# VDC.net
KiCad netlist of a schematic drawn in EAGLE
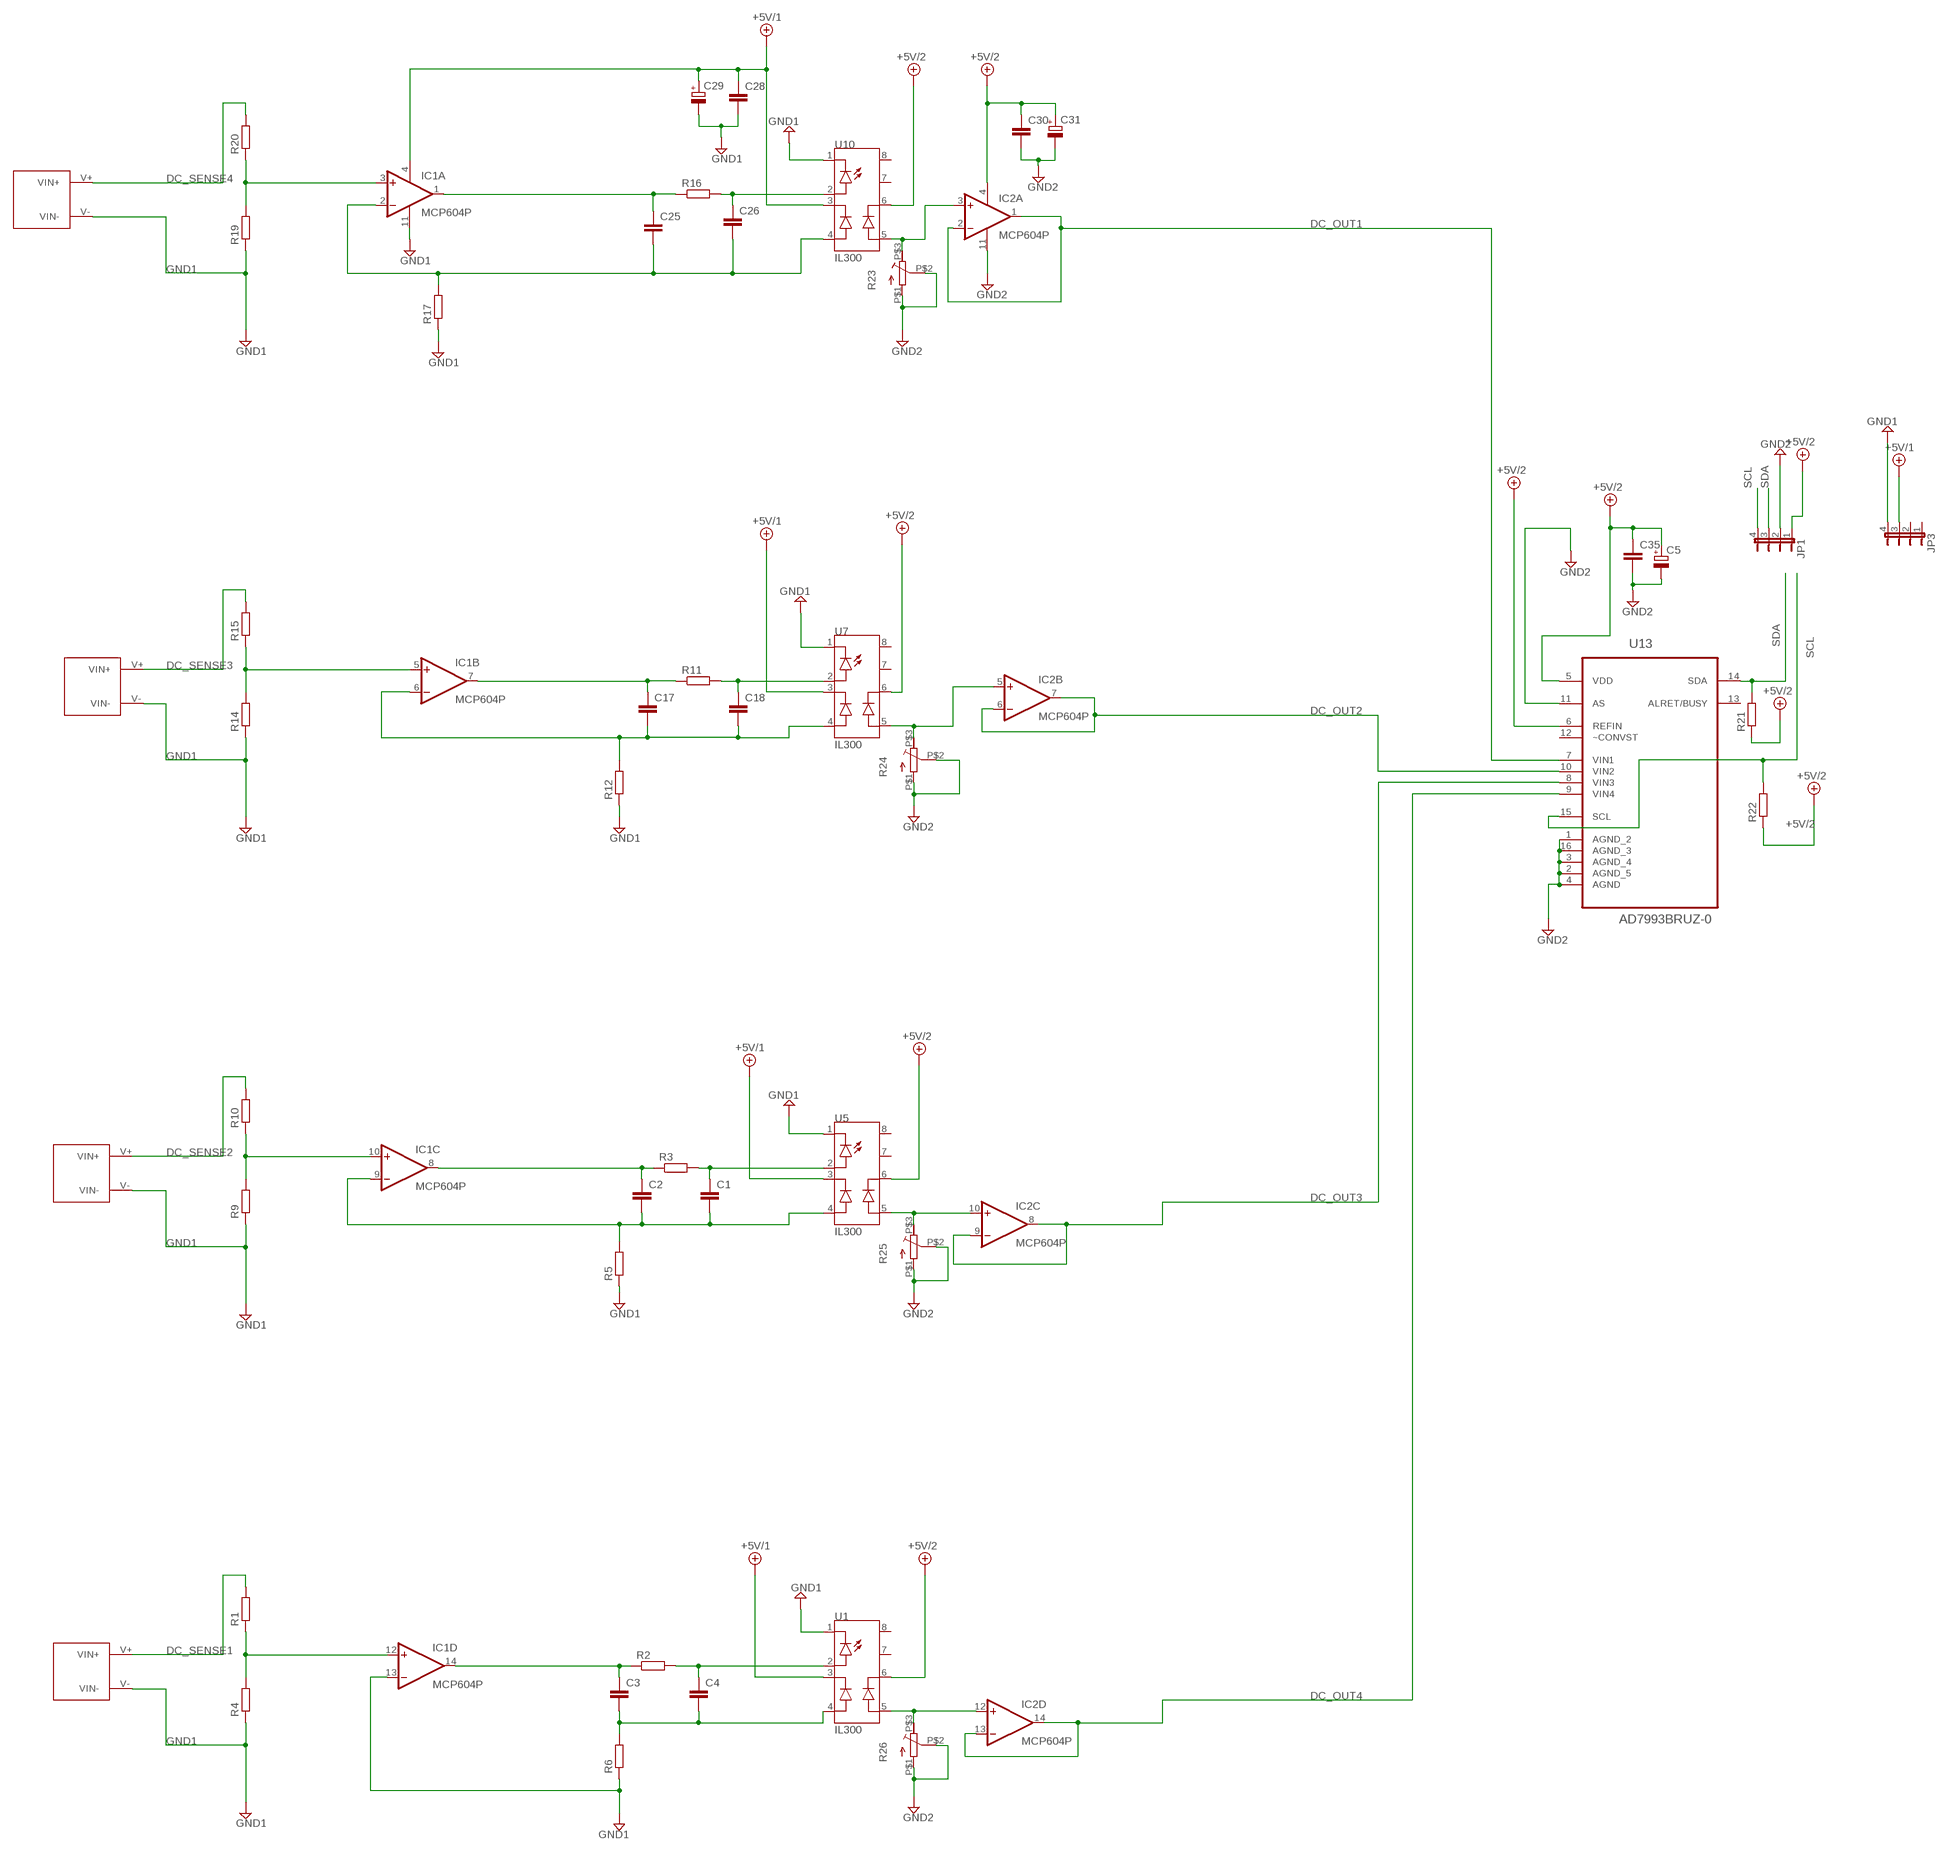
[diagram p0: schematic, sheet 1]

(export (version "E")
  (design (tool "Eeschema 10.0.6"))
  (components
    (comp (ref "C1")
      (value "C-EU025-040X050")
      (footprint "eagle-import:C025-040X050")
      (libsource (lib "eagle-import") (part "C-EU025-040X050"))
    )
    (comp (ref "C2")
      (value "C-EU025-040X050")
      (footprint "eagle-import:C025-040X050")
      (libsource (lib "eagle-import") (part "C-EU025-040X050"))
    )
    (comp (ref "C3")
      (value "C-EU025-040X050")
      (footprint "eagle-import:C025-040X050")
      (libsource (lib "eagle-import") (part "C-EU025-040X050"))
    )
    (comp (ref "C4")
      (value "C-EU025-040X050")
      (footprint "eagle-import:C025-040X050")
      (libsource (lib "eagle-import") (part "C-EU025-040X050"))
    )
    (comp (ref "C5")
      (value "CPOL-EUE2-4")
      (footprint "eagle-import:E2-4")
      (libsource (lib "eagle-import") (part "CPOL-EUE2-4"))
    )
    (comp (ref "C17")
      (value "C-EU025-040X050")
      (footprint "eagle-import:C025-040X050")
      (libsource (lib "eagle-import") (part "C-EU025-040X050"))
    )
    (comp (ref "C18")
      (value "C-EU025-040X050")
      (footprint "eagle-import:C025-040X050")
      (libsource (lib "eagle-import") (part "C-EU025-040X050"))
    )
    (comp (ref "C25")
      (value "C-EU025-040X050")
      (footprint "eagle-import:C025-040X050")
      (libsource (lib "eagle-import") (part "C-EU025-040X050"))
    )
    (comp (ref "C26")
      (value "C-EU025-040X050")
      (footprint "eagle-import:C025-040X050")
      (libsource (lib "eagle-import") (part "C-EU025-040X050"))
    )
    (comp (ref "C28")
      (value "C-EU025-040X050")
      (footprint "eagle-import:C025-040X050")
      (libsource (lib "eagle-import") (part "C-EU025-040X050"))
    )
    (comp (ref "C29")
      (value "CPOL-EUE2-5")
      (footprint "eagle-import:E2-5")
      (libsource (lib "eagle-import") (part "CPOL-EUE2-5"))
    )
    (comp (ref "C30")
      (value "C-EU025-040X050")
      (footprint "eagle-import:C025-040X050")
      (libsource (lib "eagle-import") (part "C-EU025-040X050"))
    )
    (comp (ref "C31")
      (value "CPOL-EUE2-5")
      (footprint "eagle-import:E2-5")
      (libsource (lib "eagle-import") (part "CPOL-EUE2-5"))
    )
    (comp (ref "C35")
      (value "C-EU025-025X050")
      (footprint "eagle-import:C025-025X050")
      (libsource (lib "eagle-import") (part "C-EU025-025X050"))
    )
    (comp (ref "IC1")
      (value "MCP604P")
      (footprint "eagle-import:DIL14")
      (libsource (lib "eagle-import") (part "MCP604P"))
    )
    (comp (ref "IC2")
      (value "MCP604P")
      (footprint "eagle-import:DIL14")
      (libsource (lib "eagle-import") (part "MCP604P"))
    )
    (comp (ref "JP1")
      (value "JP4E")
      (footprint "eagle-import:JP4")
      (libsource (lib "eagle-import") (part "JP4E"))
    )
    (comp (ref "JP3")
      (value "JP4E")
      (footprint "eagle-import:JP4")
      (libsource (lib "eagle-import") (part "JP4E"))
    )
    (comp (ref "R1")
      (value "R-EU_0207/10")
      (footprint "eagle-import:0207_10")
      (libsource (lib "eagle-import") (part "R-EU_0207/10"))
    )
    (comp (ref "R2")
      (value "R-EU_0207/10")
      (footprint "eagle-import:0207_10")
      (libsource (lib "eagle-import") (part "R-EU_0207/10"))
    )
    (comp (ref "R3")
      (value "R-EU_0207/10")
      (footprint "eagle-import:0207_10")
      (libsource (lib "eagle-import") (part "R-EU_0207/10"))
    )
    (comp (ref "R4")
      (value "R-EU_0207/10")
      (footprint "eagle-import:0207_10")
      (libsource (lib "eagle-import") (part "R-EU_0207/10"))
    )
    (comp (ref "R5")
      (value "R-EU_0207/10")
      (footprint "eagle-import:0207_10")
      (libsource (lib "eagle-import") (part "R-EU_0207/10"))
    )
    (comp (ref "R6")
      (value "R-EU_0207/10")
      (footprint "eagle-import:0207_10")
      (libsource (lib "eagle-import") (part "R-EU_0207/10"))
    )
    (comp (ref "R9")
      (value "R-EU_0207/10")
      (footprint "eagle-import:0207_10")
      (libsource (lib "eagle-import") (part "R-EU_0207/10"))
    )
    (comp (ref "R10")
      (value "R-EU_0207/10")
      (footprint "eagle-import:0207_10")
      (libsource (lib "eagle-import") (part "R-EU_0207/10"))
    )
    (comp (ref "R11")
      (value "R-EU_0207/10")
      (footprint "eagle-import:0207_10")
      (libsource (lib "eagle-import") (part "R-EU_0207/10"))
    )
    (comp (ref "R12")
      (value "R-EU_0207/10")
      (footprint "eagle-import:0207_10")
      (libsource (lib "eagle-import") (part "R-EU_0207/10"))
    )
    (comp (ref "R14")
      (value "R-EU_0207/10")
      (footprint "eagle-import:0207_10")
      (libsource (lib "eagle-import") (part "R-EU_0207/10"))
    )
    (comp (ref "R15")
      (value "R-EU_0207/10")
      (footprint "eagle-import:0207_10")
      (libsource (lib "eagle-import") (part "R-EU_0207/10"))
    )
    (comp (ref "R16")
      (value "R-EU_0207/10")
      (footprint "eagle-import:0207_10")
      (libsource (lib "eagle-import") (part "R-EU_0207/10"))
    )
    (comp (ref "R17")
      (value "R-EU_0207/10")
      (footprint "eagle-import:0207_10")
      (libsource (lib "eagle-import") (part "R-EU_0207/10"))
    )
    (comp (ref "R19")
      (value "R-EU_0207/10")
      (footprint "eagle-import:0207_10")
      (libsource (lib "eagle-import") (part "R-EU_0207/10"))
    )
    (comp (ref "R20")
      (value "R-EU_0207/10")
      (footprint "eagle-import:0207_10")
      (libsource (lib "eagle-import") (part "R-EU_0207/10"))
    )
    (comp (ref "R21")
      (value "R-EU_0207/10")
      (footprint "eagle-import:0207_10")
      (libsource (lib "eagle-import") (part "R-EU_0207/10"))
    )
    (comp (ref "R22")
      (value "R-EU_0207/10")
      (footprint "eagle-import:0207_10")
      (libsource (lib "eagle-import") (part "R-EU_0207/10"))
    )
    (comp (ref "R23")
      (value "R-TRIMM")
      (footprint "eagle-import:IRG2014TRIM")
      (libsource (lib "eagle-import") (part "R-TRIMM"))
    )
    (comp (ref "R24")
      (value "R-TRIMM")
      (footprint "eagle-import:IRG2014TRIM")
      (libsource (lib "eagle-import") (part "R-TRIMM"))
    )
    (comp (ref "R25")
      (value "R-TRIMM")
      (footprint "eagle-import:IRG2014TRIM")
      (libsource (lib "eagle-import") (part "R-TRIMM"))
    )
    (comp (ref "R26")
      (value "R-TRIMM")
      (footprint "eagle-import:IRG2014TRIM")
      (libsource (lib "eagle-import") (part "R-TRIMM"))
    )
    (comp (ref "U$5")
      (value "INPUT_VOLTAGE_CONNECTOR")
      (footprint "eagle-import:INPUT_VOLTAGE_CONNECTOR")
      (libsource (lib "eagle-import") (part "INPUT_VOLTAGE_CONNECTOR"))
    )
    (comp (ref "U$6")
      (value "INPUT_VOLTAGE_CONNECTOR")
      (footprint "eagle-import:INPUT_VOLTAGE_CONNECTOR")
      (libsource (lib "eagle-import") (part "INPUT_VOLTAGE_CONNECTOR"))
    )
    (comp (ref "U$7")
      (value "INPUT_VOLTAGE_CONNECTOR")
      (footprint "eagle-import:INPUT_VOLTAGE_CONNECTOR")
      (libsource (lib "eagle-import") (part "INPUT_VOLTAGE_CONNECTOR"))
    )
    (comp (ref "U$8")
      (value "INPUT_VOLTAGE_CONNECTOR")
      (footprint "eagle-import:INPUT_VOLTAGE_CONNECTOR")
      (libsource (lib "eagle-import") (part "INPUT_VOLTAGE_CONNECTOR"))
    )
    (comp (ref "U1")
      (value "IL300")
      (footprint "eagle-import:DIL08")
      (libsource (lib "eagle-import") (part "IL300"))
    )
    (comp (ref "U5")
      (value "IL300")
      (footprint "eagle-import:DIL08")
      (libsource (lib "eagle-import") (part "IL300"))
    )
    (comp (ref "U7")
      (value "IL300")
      (footprint "eagle-import:DIL08")
      (libsource (lib "eagle-import") (part "IL300"))
    )
    (comp (ref "U10")
      (value "IL300")
      (footprint "eagle-import:DIL08")
      (libsource (lib "eagle-import") (part "IL300"))
    )
    (comp (ref "U13")
      (value "AD7993BRUZ-0")
      (footprint "eagle-import:SOP65P640X120-16N")
      (libsource (lib "eagle-import") (part "AD7993BRUZ-0"))
    )
  )
  (nets
    (net (code "1") (name "+5V{slash}1") (class "Default")
      (node (ref "C28") (pin "1") (pinfunction "1_1") (pintype "passive"))
      (node (ref "C29") (pin "+") (pinfunction "+_+") (pintype "passive"))
      (node (ref "IC1") (pin "4") (pinfunction "V+_4") (pintype "power_in"))
      (node (ref "JP3") (pin "3") (pinfunction "3_3") (pintype "passive"))
      (node (ref "U1") (pin "3") (pinfunction "C_FB_3") (pintype "passive"))
      (node (ref "U10") (pin "3") (pinfunction "C_FB_3") (pintype "passive"))
      (node (ref "U5") (pin "3") (pinfunction "C_FB_3") (pintype "passive"))
      (node (ref "U7") (pin "3") (pinfunction "C_FB_3") (pintype "passive"))
    )
    (net (code "2") (name "+5V{slash}2") (class "Default")
      (node (ref "C30") (pin "1") (pinfunction "1_1") (pintype "passive"))
      (node (ref "C31") (pin "+") (pinfunction "+_+") (pintype "passive"))
      (node (ref "C35") (pin "1") (pinfunction "1_1") (pintype "passive"))
      (node (ref "C5") (pin "+") (pinfunction "+_+") (pintype "passive"))
      (node (ref "IC2") (pin "4") (pinfunction "V+_4") (pintype "power_in"))
      (node (ref "JP1") (pin "1") (pinfunction "1_1") (pintype "passive"))
      (node (ref "R21") (pin "1") (pinfunction "1_1") (pintype "passive"))
      (node (ref "R22") (pin "1") (pinfunction "1_1") (pintype "passive"))
      (node (ref "U1") (pin "6") (pinfunction "C_OUT_6") (pintype "passive"))
      (node (ref "U10") (pin "6") (pinfunction "C_OUT_6") (pintype "passive"))
      (node (ref "U13") (pin "5") (pinfunction "VDD_5") (pintype "power_in"))
      (node (ref "U13") (pin "6") (pinfunction "REFIN_6") (pintype "input"))
      (node (ref "U5") (pin "6") (pinfunction "C_OUT_6") (pintype "passive"))
      (node (ref "U7") (pin "6") (pinfunction "C_OUT_6") (pintype "passive"))
    )
    (net (code "3") (name "/DC_OUT1") (class "Default")
      (node (ref "IC2") (pin "1") (pinfunction "OUT_1") (pintype "output"))
      (node (ref "IC2") (pin "2") (pinfunction "-IN_2") (pintype "input"))
      (node (ref "U13") (pin "7") (pinfunction "VIN1_7") (pintype "input"))
    )
    (net (code "4") (name "/DC_OUT2") (class "Default")
      (node (ref "IC2") (pin "6") (pinfunction "-IN_6") (pintype "input"))
      (node (ref "IC2") (pin "7") (pinfunction "OUT_7") (pintype "output"))
      (node (ref "U13") (pin "10") (pinfunction "VIN2_10") (pintype "input"))
    )
    (net (code "5") (name "/DC_OUT3") (class "Default")
      (node (ref "IC2") (pin "8") (pinfunction "OUT_8") (pintype "output"))
      (node (ref "IC2") (pin "9") (pinfunction "-IN_9") (pintype "input"))
      (node (ref "U13") (pin "8") (pinfunction "VIN3_8") (pintype "input"))
    )
    (net (code "6") (name "/DC_OUT4") (class "Default")
      (node (ref "IC2") (pin "13") (pinfunction "-IN_13") (pintype "input"))
      (node (ref "IC2") (pin "14") (pinfunction "OUT_14") (pintype "output"))
      (node (ref "U13") (pin "9") (pinfunction "VIN4_9") (pintype "input"))
    )
    (net (code "7") (name "/DC_SENSE1") (class "Default")
      (node (ref "R1") (pin "2") (pinfunction "2_2") (pintype "passive"))
      (node (ref "U$8") (pin "V+") (pinfunction "VIN+_V+") (pintype "bidirectional"))
    )
    (net (code "8") (name "/DC_SENSE2") (class "Default")
      (node (ref "R10") (pin "2") (pinfunction "2_2") (pintype "passive"))
      (node (ref "U$7") (pin "V+") (pinfunction "VIN+_V+") (pintype "bidirectional"))
    )
    (net (code "9") (name "/DC_SENSE3") (class "Default")
      (node (ref "R15") (pin "2") (pinfunction "2_2") (pintype "passive"))
      (node (ref "U$6") (pin "V+") (pinfunction "VIN+_V+") (pintype "bidirectional"))
    )
    (net (code "10") (name "/DC_SENSE4") (class "Default")
      (node (ref "R20") (pin "2") (pinfunction "2_2") (pintype "passive"))
      (node (ref "U$5") (pin "V+") (pinfunction "VIN+_V+") (pintype "bidirectional"))
    )
    (net (code "11") (name "/SCL") (class "Default")
      (node (ref "JP1") (pin "4") (pinfunction "4_4") (pintype "passive"))
      (node (ref "R22") (pin "2") (pinfunction "2_2") (pintype "passive"))
      (node (ref "U13") (pin "15") (pinfunction "SCL_15") (pintype "input"))
    )
    (net (code "12") (name "/SDA") (class "Default")
      (node (ref "JP1") (pin "3") (pinfunction "3_3") (pintype "passive"))
      (node (ref "R21") (pin "2") (pinfunction "2_2") (pintype "passive"))
      (node (ref "U13") (pin "14") (pinfunction "SDA_14") (pintype "bidirectional"))
    )
    (net (code "13") (name "GND1") (class "Default")
      (node (ref "C28") (pin "2") (pinfunction "2_2") (pintype "passive"))
      (node (ref "C29") (pin "-") (pinfunction "-_-") (pintype "passive"))
      (node (ref "IC1") (pin "11") (pinfunction "V-_11") (pintype "power_in"))
      (node (ref "IC1") (pin "13") (pinfunction "-IN_13") (pintype "input"))
      (node (ref "JP3") (pin "4") (pinfunction "4_4") (pintype "passive"))
      (node (ref "R12") (pin "1") (pinfunction "1_1") (pintype "passive"))
      (node (ref "R14") (pin "1") (pinfunction "1_1") (pintype "passive"))
      (node (ref "R17") (pin "1") (pinfunction "1_1") (pintype "passive"))
      (node (ref "R19") (pin "1") (pinfunction "1_1") (pintype "passive"))
      (node (ref "R4") (pin "1") (pinfunction "1_1") (pintype "passive"))
      (node (ref "R5") (pin "1") (pinfunction "1_1") (pintype "passive"))
      (node (ref "R6") (pin "1") (pinfunction "1_1") (pintype "passive"))
      (node (ref "R9") (pin "1") (pinfunction "1_1") (pintype "passive"))
      (node (ref "U$5") (pin "V-") (pinfunction "VIN-_V-") (pintype "bidirectional"))
      (node (ref "U$6") (pin "V-") (pinfunction "VIN-_V-") (pintype "bidirectional"))
      (node (ref "U$7") (pin "V-") (pinfunction "VIN-_V-") (pintype "bidirectional"))
      (node (ref "U$8") (pin "V-") (pinfunction "VIN-_V-") (pintype "bidirectional"))
      (node (ref "U1") (pin "1") (pinfunction "C_LED_1") (pintype "passive"))
      (node (ref "U10") (pin "1") (pinfunction "C_LED_1") (pintype "passive"))
      (node (ref "U5") (pin "1") (pinfunction "C_LED_1") (pintype "passive"))
      (node (ref "U7") (pin "1") (pinfunction "C_LED_1") (pintype "passive"))
    )
    (net (code "14") (name "GND2") (class "Default")
      (node (ref "C30") (pin "2") (pinfunction "2_2") (pintype "passive"))
      (node (ref "C31") (pin "-") (pinfunction "-_-") (pintype "passive"))
      (node (ref "C35") (pin "2") (pinfunction "2_2") (pintype "passive"))
      (node (ref "C5") (pin "-") (pinfunction "-_-") (pintype "passive"))
      (node (ref "IC2") (pin "11") (pinfunction "V-_11") (pintype "power_in"))
      (node (ref "JP1") (pin "2") (pinfunction "2_2") (pintype "passive"))
      (node (ref "R23") (pin "P$1") (pinfunction "A_P$1") (pintype "passive"))
      (node (ref "R23") (pin "P$2") (pinfunction "S_P$2") (pintype "passive"))
      (node (ref "R24") (pin "P$1") (pinfunction "A_P$1") (pintype "passive"))
      (node (ref "R24") (pin "P$2") (pinfunction "S_P$2") (pintype "passive"))
      (node (ref "R25") (pin "P$1") (pinfunction "A_P$1") (pintype "passive"))
      (node (ref "R25") (pin "P$2") (pinfunction "S_P$2") (pintype "passive"))
      (node (ref "R26") (pin "P$1") (pinfunction "A_P$1") (pintype "passive"))
      (node (ref "R26") (pin "P$2") (pinfunction "S_P$2") (pintype "passive"))
      (node (ref "U13") (pin "1") (pinfunction "AGND_2_1") (pintype "passive"))
      (node (ref "U13") (pin "11") (pinfunction "AS_11") (pintype "input"))
      (node (ref "U13") (pin "16") (pinfunction "AGND_3_16") (pintype "passive"))
      (node (ref "U13") (pin "2") (pinfunction "AGND_5_2") (pintype "passive"))
      (node (ref "U13") (pin "3") (pinfunction "AGND_4_3") (pintype "passive"))
      (node (ref "U13") (pin "4") (pinfunction "AGND_4") (pintype "passive"))
    )
    (net (code "15") (name "Net-(IC1A-+IN)") (class "Default")
      (node (ref "IC1") (pin "3") (pinfunction "+IN_3") (pintype "input"))
      (node (ref "R19") (pin "2") (pinfunction "2_2") (pintype "passive"))
      (node (ref "R20") (pin "1") (pinfunction "1_1") (pintype "passive"))
    )
    (net (code "16") (name "Net-(IC1A--IN)") (class "Default")
      (node (ref "C25") (pin "2") (pinfunction "2_2") (pintype "passive"))
      (node (ref "C26") (pin "2") (pinfunction "2_2") (pintype "passive"))
      (node (ref "IC1") (pin "2") (pinfunction "-IN_2") (pintype "input"))
      (node (ref "R17") (pin "2") (pinfunction "2_2") (pintype "passive"))
      (node (ref "U10") (pin "4") (pinfunction "A_FB_4") (pintype "passive"))
    )
    (net (code "17") (name "Net-(IC1A-OUT)") (class "Default")
      (node (ref "C25") (pin "1") (pinfunction "1_1") (pintype "passive"))
      (node (ref "IC1") (pin "1") (pinfunction "OUT_1") (pintype "output"))
      (node (ref "R16") (pin "1") (pinfunction "1_1") (pintype "passive"))
    )
    (net (code "18") (name "Net-(IC1B-+IN)") (class "Default")
      (node (ref "IC1") (pin "5") (pinfunction "+IN_5") (pintype "input"))
      (node (ref "R14") (pin "2") (pinfunction "2_2") (pintype "passive"))
      (node (ref "R15") (pin "1") (pinfunction "1_1") (pintype "passive"))
    )
    (net (code "19") (name "Net-(IC1B--IN)") (class "Default")
      (node (ref "C17") (pin "2") (pinfunction "2_2") (pintype "passive"))
      (node (ref "C18") (pin "2") (pinfunction "2_2") (pintype "passive"))
      (node (ref "IC1") (pin "6") (pinfunction "-IN_6") (pintype "input"))
      (node (ref "R12") (pin "2") (pinfunction "2_2") (pintype "passive"))
      (node (ref "U7") (pin "4") (pinfunction "A_FB_4") (pintype "passive"))
    )
    (net (code "20") (name "Net-(IC1B-OUT)") (class "Default")
      (node (ref "C17") (pin "1") (pinfunction "1_1") (pintype "passive"))
      (node (ref "IC1") (pin "7") (pinfunction "OUT_7") (pintype "output"))
      (node (ref "R11") (pin "1") (pinfunction "1_1") (pintype "passive"))
    )
    (net (code "21") (name "Net-(IC1C-+IN)") (class "Default")
      (node (ref "IC1") (pin "10") (pinfunction "+IN_10") (pintype "input"))
      (node (ref "R10") (pin "1") (pinfunction "1_1") (pintype "passive"))
      (node (ref "R9") (pin "2") (pinfunction "2_2") (pintype "passive"))
    )
    (net (code "22") (name "Net-(IC1C--IN)") (class "Default")
      (node (ref "C1") (pin "2") (pinfunction "2_2") (pintype "passive"))
      (node (ref "C2") (pin "2") (pinfunction "2_2") (pintype "passive"))
      (node (ref "IC1") (pin "9") (pinfunction "-IN_9") (pintype "input"))
      (node (ref "R5") (pin "2") (pinfunction "2_2") (pintype "passive"))
      (node (ref "U5") (pin "4") (pinfunction "A_FB_4") (pintype "passive"))
    )
    (net (code "23") (name "Net-(IC1C-OUT)") (class "Default")
      (node (ref "C2") (pin "1") (pinfunction "1_1") (pintype "passive"))
      (node (ref "IC1") (pin "8") (pinfunction "OUT_8") (pintype "output"))
      (node (ref "R3") (pin "1") (pinfunction "1_1") (pintype "passive"))
    )
    (net (code "24") (name "Net-(IC1D-+IN)") (class "Default")
      (node (ref "IC1") (pin "12") (pinfunction "+IN_12") (pintype "input"))
      (node (ref "R1") (pin "1") (pinfunction "1_1") (pintype "passive"))
      (node (ref "R4") (pin "2") (pinfunction "2_2") (pintype "passive"))
    )
    (net (code "25") (name "Net-(IC1D-OUT)") (class "Default")
      (node (ref "C3") (pin "1") (pinfunction "1_1") (pintype "passive"))
      (node (ref "IC1") (pin "14") (pinfunction "OUT_14") (pintype "output"))
      (node (ref "R2") (pin "1") (pinfunction "1_1") (pintype "passive"))
    )
    (net (code "26") (name "Net-(IC2A-+IN)") (class "Default")
      (node (ref "IC2") (pin "3") (pinfunction "+IN_3") (pintype "input"))
      (node (ref "R23") (pin "P$3") (pinfunction "E_P$3") (pintype "passive"))
      (node (ref "U10") (pin "5") (pinfunction "A_OUT_5") (pintype "passive"))
    )
    (net (code "27") (name "Net-(IC2B-+IN)") (class "Default")
      (node (ref "IC2") (pin "5") (pinfunction "+IN_5") (pintype "input"))
      (node (ref "R24") (pin "P$3") (pinfunction "E_P$3") (pintype "passive"))
      (node (ref "U7") (pin "5") (pinfunction "A_OUT_5") (pintype "passive"))
    )
    (net (code "28") (name "Net-(IC2C-+IN)") (class "Default")
      (node (ref "IC2") (pin "10") (pinfunction "+IN_10") (pintype "input"))
      (node (ref "R25") (pin "P$3") (pinfunction "E_P$3") (pintype "passive"))
      (node (ref "U5") (pin "5") (pinfunction "A_OUT_5") (pintype "passive"))
    )
    (net (code "29") (name "Net-(IC2D-+IN)") (class "Default")
      (node (ref "IC2") (pin "12") (pinfunction "+IN_12") (pintype "input"))
      (node (ref "R26") (pin "P$3") (pinfunction "E_P$3") (pintype "passive"))
      (node (ref "U1") (pin "5") (pinfunction "A_OUT_5") (pintype "passive"))
    )
    (net (code "30") (name "Net-(U1-A_FB)") (class "Default")
      (node (ref "C3") (pin "2") (pinfunction "2_2") (pintype "passive"))
      (node (ref "C4") (pin "2") (pinfunction "2_2") (pintype "passive"))
      (node (ref "R6") (pin "2") (pinfunction "2_2") (pintype "passive"))
      (node (ref "U1") (pin "4") (pinfunction "A_FB_4") (pintype "passive"))
    )
    (net (code "31") (name "Net-(U1-A_LED)") (class "Default")
      (node (ref "C4") (pin "1") (pinfunction "1_1") (pintype "passive"))
      (node (ref "R2") (pin "2") (pinfunction "2_2") (pintype "passive"))
      (node (ref "U1") (pin "2") (pinfunction "A_LED_2") (pintype "passive"))
    )
    (net (code "32") (name "Net-(U5-A_LED)") (class "Default")
      (node (ref "C1") (pin "1") (pinfunction "1_1") (pintype "passive"))
      (node (ref "R3") (pin "2") (pinfunction "2_2") (pintype "passive"))
      (node (ref "U5") (pin "2") (pinfunction "A_LED_2") (pintype "passive"))
    )
    (net (code "33") (name "Net-(U7-A_LED)") (class "Default")
      (node (ref "C18") (pin "1") (pinfunction "1_1") (pintype "passive"))
      (node (ref "R11") (pin "2") (pinfunction "2_2") (pintype "passive"))
      (node (ref "U7") (pin "2") (pinfunction "A_LED_2") (pintype "passive"))
    )
    (net (code "34") (name "Net-(U10-A_LED)") (class "Default")
      (node (ref "C26") (pin "1") (pinfunction "1_1") (pintype "passive"))
      (node (ref "R16") (pin "2") (pinfunction "2_2") (pintype "passive"))
      (node (ref "U10") (pin "2") (pinfunction "A_LED_2") (pintype "passive"))
    )
    (net (code "35") (name "unconnected-(JP3-Pad1)") (class "Default")
      (node (ref "JP3") (pin "1") (pinfunction "1_1") (pintype "passive"))
    )
    (net (code "36") (name "unconnected-(JP3-Pad2)") (class "Default")
      (node (ref "JP3") (pin "2") (pinfunction "2_2") (pintype "passive"))
    )
    (net (code "37") (name "unconnected-(U1-PIN7-Pad7)") (class "Default")
      (node (ref "U1") (pin "7") (pinfunction "PIN7_7") (pintype "no_connect"))
    )
    (net (code "38") (name "unconnected-(U1-PIN8-Pad8)") (class "Default")
      (node (ref "U1") (pin "8") (pinfunction "PIN8_8") (pintype "no_connect"))
    )
    (net (code "39") (name "unconnected-(U5-PIN7-Pad7)") (class "Default")
      (node (ref "U5") (pin "7") (pinfunction "PIN7_7") (pintype "no_connect"))
    )
    (net (code "40") (name "unconnected-(U5-PIN8-Pad8)") (class "Default")
      (node (ref "U5") (pin "8") (pinfunction "PIN8_8") (pintype "no_connect"))
    )
    (net (code "41") (name "unconnected-(U7-PIN7-Pad7)") (class "Default")
      (node (ref "U7") (pin "7") (pinfunction "PIN7_7") (pintype "no_connect"))
    )
    (net (code "42") (name "unconnected-(U7-PIN8-Pad8)") (class "Default")
      (node (ref "U7") (pin "8") (pinfunction "PIN8_8") (pintype "no_connect"))
    )
    (net (code "43") (name "unconnected-(U10-PIN7-Pad7)") (class "Default")
      (node (ref "U10") (pin "7") (pinfunction "PIN7_7") (pintype "no_connect"))
    )
    (net (code "44") (name "unconnected-(U10-PIN8-Pad8)") (class "Default")
      (node (ref "U10") (pin "8") (pinfunction "PIN8_8") (pintype "no_connect"))
    )
    (net (code "45") (name "unconnected-(U13-ALRET{slash}BUSY-Pad13)") (class "Default")
      (node (ref "U13") (pin "13") (pinfunction "ALRET/BUSY_13") (pintype "output"))
    )
    (net (code "46") (name "unconnected-(U13-~{CONVST}-Pad12)") (class "Default")
      (node (ref "U13") (pin "12") (pinfunction "~{CONVST}_12") (pintype "input"))
    )
  )
)
